# stm32f103_pin1.net
KiCad netlist of a schematic drawn in EAGLE
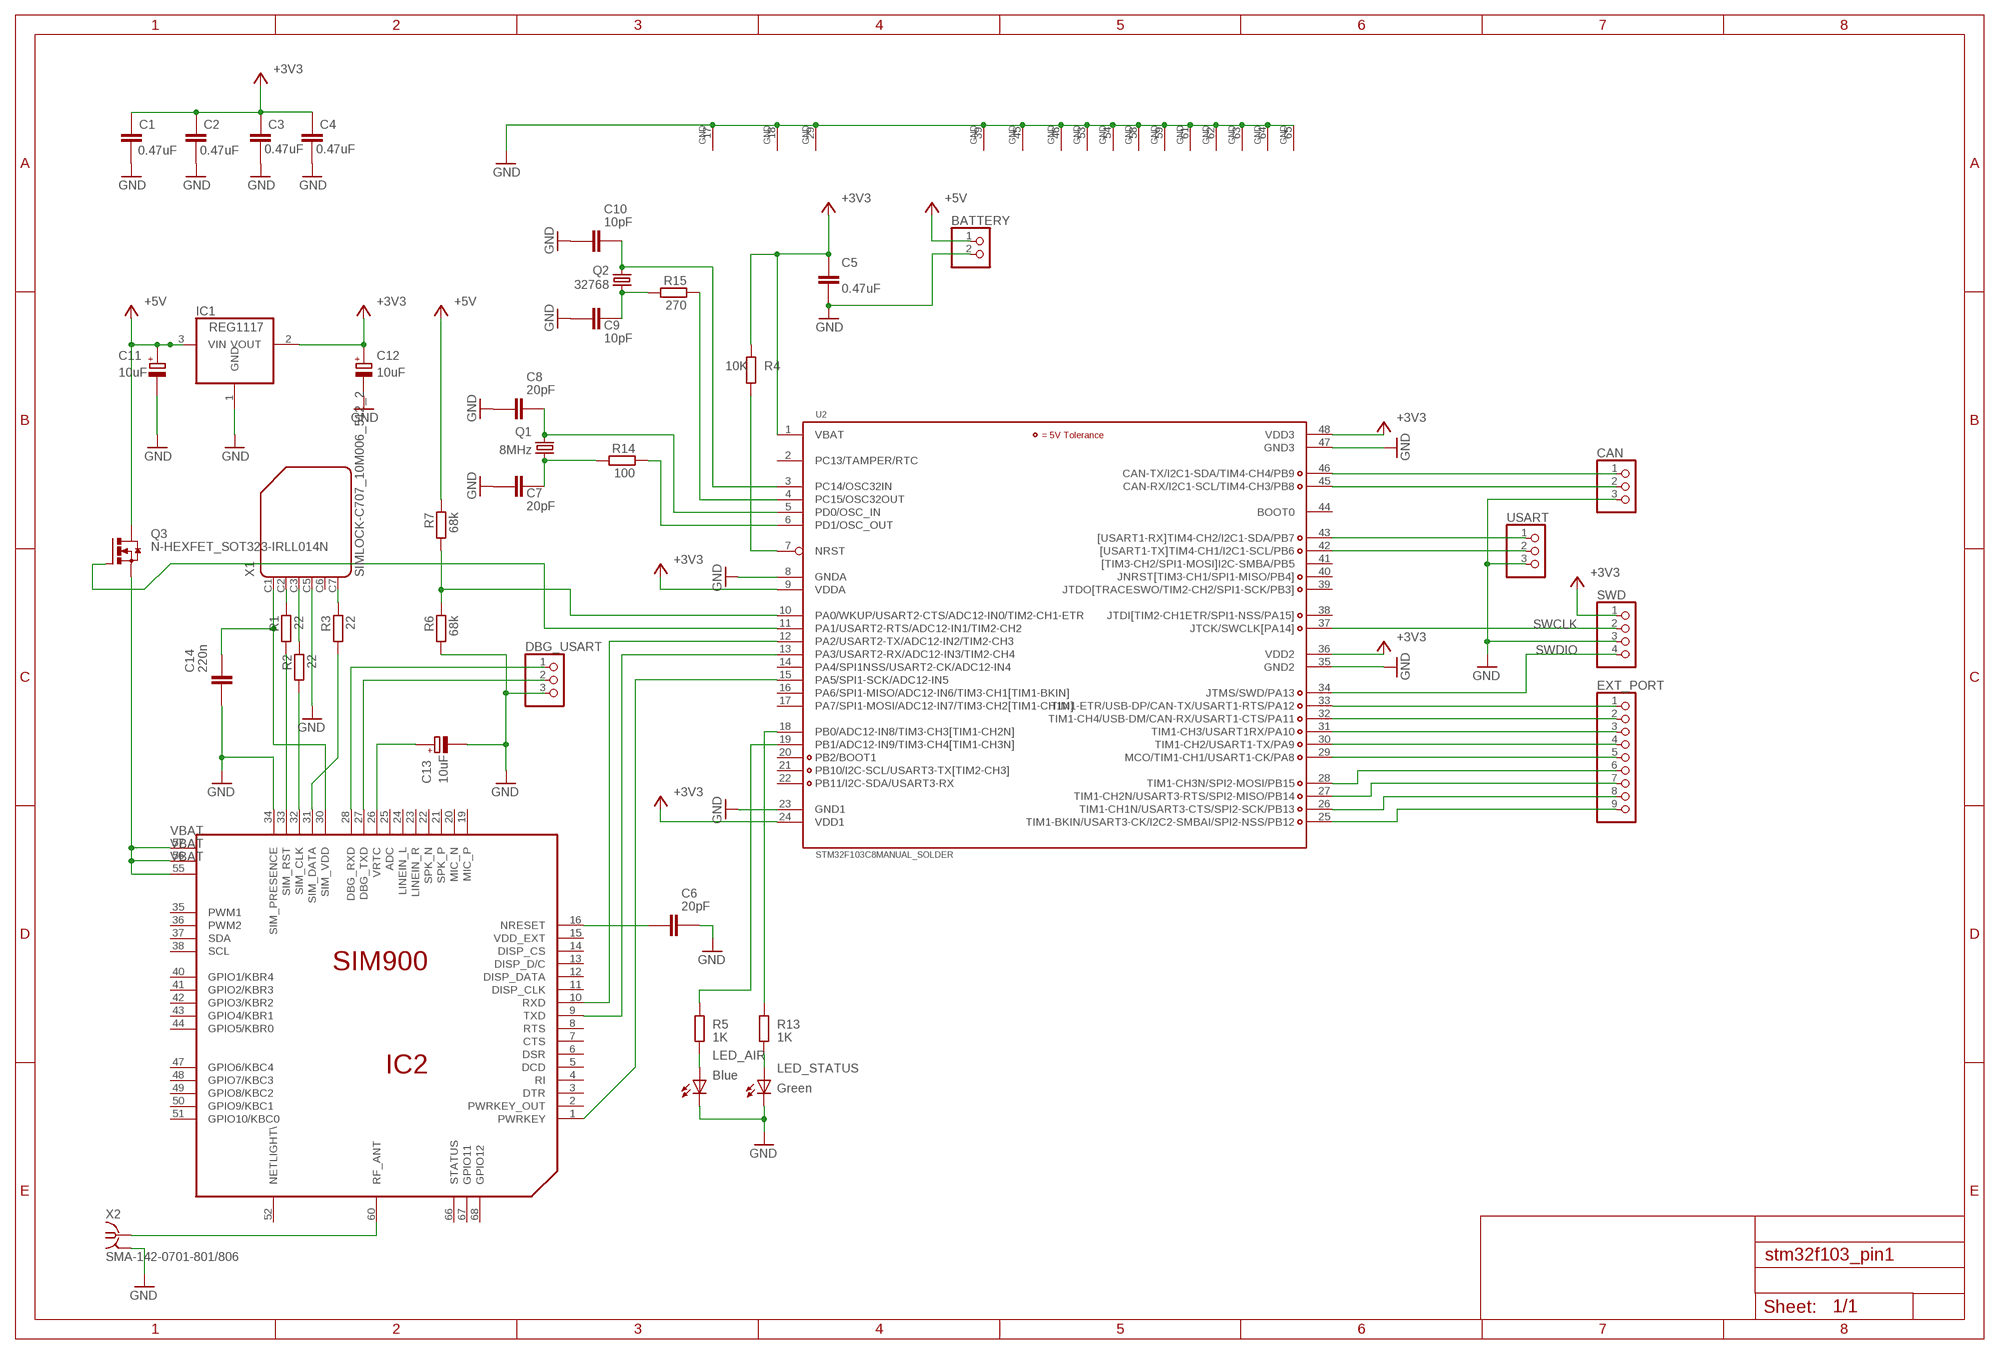
[diagram p0: schematic, sheet 1]

(export (version "E")
  (design (tool "Eeschema 10.0.6"))
  (components
    (comp (ref "BATTERY")
      (value "PINHD-1X2")
      (footprint "eagle-import:1X02")
      (libsource (lib "eagle-import") (part "PINHD-1X2"))
    )
    (comp (ref "C1")
      (value "0.47uF")
      (footprint "eagle-import:CAPC2012X145AN")
      (libsource (lib "eagle-import") (part "CAPACITOR_0805"))
    )
    (comp (ref "C2")
      (value "0.47uF")
      (footprint "eagle-import:CAPC2012X145AN")
      (libsource (lib "eagle-import") (part "CAPACITOR_0805"))
    )
    (comp (ref "C3")
      (value "0.47uF")
      (footprint "eagle-import:CAPC2012X145AN")
      (libsource (lib "eagle-import") (part "CAPACITOR_0805"))
    )
    (comp (ref "C4")
      (value "0.47uF")
      (footprint "eagle-import:CAPC2012X145AN")
      (libsource (lib "eagle-import") (part "CAPACITOR_0805"))
    )
    (comp (ref "C5")
      (value "0.47uF")
      (footprint "eagle-import:CAPC2012X145AN")
      (libsource (lib "eagle-import") (part "CAPACITOR_0805"))
    )
    (comp (ref "C6")
      (value "20pF")
      (footprint "eagle-import:CAPC2012X145AN")
      (libsource (lib "eagle-import") (part "CAPACITOR_0805"))
    )
    (comp (ref "C7")
      (value "20pF")
      (footprint "eagle-import:CAPC2012X145AN")
      (libsource (lib "eagle-import") (part "CAPACITOR_0805"))
    )
    (comp (ref "C8")
      (value "20pF")
      (footprint "eagle-import:CAPC2012X145AN")
      (libsource (lib "eagle-import") (part "CAPACITOR_0805"))
    )
    (comp (ref "C9")
      (value "10pF")
      (footprint "eagle-import:CAPC2012X145AN")
      (libsource (lib "eagle-import") (part "CAPACITOR_0805"))
    )
    (comp (ref "C10")
      (value "10pF")
      (footprint "eagle-import:CAPC2012X145AN")
      (libsource (lib "eagle-import") (part "CAPACITOR_0805"))
    )
    (comp (ref "C11")
      (value "10uF")
      (footprint "eagle-import:CAPMP3216X180N")
      (libsource (lib "eagle-import") (part "POLARISED_A_CASE"))
    )
    (comp (ref "C12")
      (value "10uF")
      (footprint "eagle-import:CAPMP3216X180N")
      (libsource (lib "eagle-import") (part "POLARISED_A_CASE"))
    )
    (comp (ref "C13")
      (value "10uF")
      (footprint "eagle-import:CAPMP3216X180N")
      (libsource (lib "eagle-import") (part "POLARISED_A_CASE"))
    )
    (comp (ref "C14")
      (value "220n")
      (footprint "eagle-import:CAPC2012X145AN")
      (libsource (lib "eagle-import") (part "CAPACITOR_0805"))
    )
    (comp (ref "CAN")
      (value "PINHD-1X3")
      (footprint "eagle-import:1X03")
      (libsource (lib "eagle-import") (part "PINHD-1X3"))
    )
    (comp (ref "DBG_USART")
      (value "PINHD-1X3")
      (footprint "eagle-import:1X03")
      (libsource (lib "eagle-import") (part "PINHD-1X3"))
    )
    (comp (ref "EXT_PORT")
      (value "PINHD-1X9")
      (footprint "eagle-import:1X09")
      (libsource (lib "eagle-import") (part "PINHD-1X9"))
    )
    (comp (ref "IC1")
      (value "REG1117")
      (footprint "eagle-import:SOT223")
      (libsource (lib "eagle-import") (part "REG1117"))
    )
    (comp (ref "IC2")
      (value "SIM900")
      (footprint "eagle-import:SIM900")
      (libsource (lib "eagle-import") (part "SIM900"))
    )
    (comp (ref "LED_AIR")
      (value "Blue")
      (footprint "eagle-import:CHIP-LED0805")
      (libsource (lib "eagle-import") (part "LEDCHIP-LED0805"))
    )
    (comp (ref "LED_STATUS")
      (value "Green")
      (footprint "eagle-import:CHIP-LED0805")
      (libsource (lib "eagle-import") (part "LEDCHIP-LED0805"))
    )
    (comp (ref "Q1")
      (value "8MHz")
      (footprint "eagle-import:HC49_S")
      (libsource (lib "eagle-import") (part "CRYSTALHC49S"))
    )
    (comp (ref "Q2")
      (value "32768")
      (footprint "eagle-import:TC38H")
      (libsource (lib "eagle-import") (part "CRYSTALTC38H"))
    )
    (comp (ref "Q3")
      (value "N-HEXFET_SOT323-IRLL014N")
      (footprint "eagle-import:SOT223")
      (libsource (lib "eagle-import") (part "N-HEXFET_?-SOT323IRLL014N"))
    )
    (comp (ref "R1")
      (value "22")
      (footprint "eagle-import:RESC2012X70N")
      (libsource (lib "eagle-import") (part "RESISTOR_0805"))
    )
    (comp (ref "R2")
      (value "22")
      (footprint "eagle-import:RESC2012X70N")
      (libsource (lib "eagle-import") (part "RESISTOR_0805"))
    )
    (comp (ref "R3")
      (value "22")
      (footprint "eagle-import:RESC2012X70N")
      (libsource (lib "eagle-import") (part "RESISTOR_0805"))
    )
    (comp (ref "R4")
      (value "10K")
      (footprint "eagle-import:RESC2012X70N")
      (libsource (lib "eagle-import") (part "RESISTOR_0805"))
    )
    (comp (ref "R5")
      (value "1K")
      (footprint "eagle-import:RESC2012X70N")
      (libsource (lib "eagle-import") (part "RESISTOR_0805"))
    )
    (comp (ref "R6")
      (value "68k")
      (footprint "eagle-import:RESC2012X70N")
      (libsource (lib "eagle-import") (part "RESISTOR_0805"))
    )
    (comp (ref "R7")
      (value "68k")
      (footprint "eagle-import:RESC2012X70N")
      (libsource (lib "eagle-import") (part "RESISTOR_0805"))
    )
    (comp (ref "R13")
      (value "1K")
      (footprint "eagle-import:RESC2012X70N")
      (libsource (lib "eagle-import") (part "RESISTOR_0805"))
    )
    (comp (ref "R14")
      (value "100")
      (footprint "eagle-import:RESC2012X70N")
      (libsource (lib "eagle-import") (part "RESISTOR_0805"))
    )
    (comp (ref "R15")
      (value "270")
      (footprint "eagle-import:RESC2012X70N")
      (libsource (lib "eagle-import") (part "RESISTOR_0805"))
    )
    (comp (ref "SWD")
      (value "PINHD-1X4")
      (footprint "eagle-import:1X04")
      (libsource (lib "eagle-import") (part "PINHD-1X4"))
    )
    (comp (ref "U2")
      (value "STM32F103C8MANUAL_SOLDER")
      (footprint "eagle-import:LQFP48_IGORL")
      (libsource (lib "eagle-import") (part "STM32F103C8MANUAL_SOLDER"))
    )
    (comp (ref "USART")
      (value "PINHD-1X3")
      (footprint "eagle-import:1X03")
      (libsource (lib "eagle-import") (part "PINHD-1X3"))
    )
    (comp (ref "X1")
      (value "SIMLOCK-C707_10M006_512_2")
      (footprint "eagle-import:C707_10M006_512_2")
      (libsource (lib "eagle-import") (part "SIMLOCK-C707_10M006_512_2"))
    )
    (comp (ref "X2")
      (value "SMA-142-0701-801/806")
      (footprint "eagle-import:J502-ND-142-0701-801_806")
      (fields (field (name "MF") "JOHNSON COMPONENTS") (field (name "MPN") "142-0701-801"))
      (libsource (lib "eagle-import") (part "SMA-142-0701-801/806"))
    )
  )
  (nets
    (net (code "1") (name "+3V3") (class "Default")
      (node (ref "C1") (pin "1") (pinfunction "1_1") (pintype "passive"))
      (node (ref "C12") (pin "+") (pinfunction "+_+") (pintype "passive"))
      (node (ref "C2") (pin "1") (pinfunction "1_1") (pintype "passive"))
      (node (ref "C3") (pin "1") (pinfunction "1_1") (pintype "passive"))
      (node (ref "C4") (pin "1") (pinfunction "1_1") (pintype "passive"))
      (node (ref "C5") (pin "1") (pinfunction "1_1") (pintype "passive"))
      (node (ref "IC1") (pin "2") (pinfunction "VOUT_2") (pintype "output"))
      (node (ref "R4") (pin "2") (pinfunction "2_2") (pintype "passive"))
      (node (ref "SWD") (pin "1") (pinfunction "1_1") (pintype "passive"))
      (node (ref "U2") (pin "1") (pinfunction "VBAT_1") (pintype "power_in"))
      (node (ref "U2") (pin "24") (pinfunction "VDD1_24") (pintype "power_in"))
      (node (ref "U2") (pin "36") (pinfunction "VDD2_36") (pintype "power_in"))
      (node (ref "U2") (pin "48") (pinfunction "VDD3_48") (pintype "power_in"))
      (node (ref "U2") (pin "9") (pinfunction "VDDA_9") (pintype "power_in"))
    )
    (net (code "2") (name "+5V") (class "Default")
      (node (ref "BATTERY") (pin "1") (pinfunction "1_1") (pintype "passive"))
      (node (ref "C11") (pin "+") (pinfunction "+_+") (pintype "passive"))
      (node (ref "IC1") (pin "3") (pinfunction "VIN_3") (pintype "input"))
      (node (ref "Q3") (pin "4") (pinfunction "D_4") (pintype "passive"))
      (node (ref "R7") (pin "1") (pinfunction "1_1") (pintype "passive"))
    )
    (net (code "3") (name "GND") (class "Default")
      (node (ref "BATTERY") (pin "2") (pinfunction "2_2") (pintype "passive"))
      (node (ref "C1") (pin "2") (pinfunction "2_2") (pintype "passive"))
      (node (ref "C10") (pin "2") (pinfunction "2_2") (pintype "passive"))
      (node (ref "C11") (pin "-") (pinfunction "-_-") (pintype "passive"))
      (node (ref "C12") (pin "-") (pinfunction "-_-") (pintype "passive"))
      (node (ref "C13") (pin "-") (pinfunction "-_-") (pintype "passive"))
      (node (ref "C14") (pin "2") (pinfunction "2_2") (pintype "passive"))
      (node (ref "C2") (pin "2") (pinfunction "2_2") (pintype "passive"))
      (node (ref "C3") (pin "2") (pinfunction "2_2") (pintype "passive"))
      (node (ref "C4") (pin "2") (pinfunction "2_2") (pintype "passive"))
      (node (ref "C5") (pin "2") (pinfunction "2_2") (pintype "passive"))
      (node (ref "C6") (pin "1") (pinfunction "1_1") (pintype "passive"))
      (node (ref "C7") (pin "2") (pinfunction "2_2") (pintype "passive"))
      (node (ref "C8") (pin "2") (pinfunction "2_2") (pintype "passive"))
      (node (ref "C9") (pin "2") (pinfunction "2_2") (pintype "passive"))
      (node (ref "CAN") (pin "3") (pinfunction "3_3") (pintype "passive"))
      (node (ref "DBG_USART") (pin "3") (pinfunction "3_3") (pintype "passive"))
      (node (ref "IC1") (pin "1") (pinfunction "GND_1") (pintype "power_in"))
      (node (ref "IC2") (pin "17") (pinfunction "GND_17") (pintype "power_in"))
      (node (ref "IC2") (pin "18") (pinfunction "GND_18") (pintype "power_in"))
      (node (ref "IC2") (pin "29") (pinfunction "GND_29") (pintype "power_in"))
      (node (ref "IC2") (pin "34") (pinfunction "SIM_PRESENCE_34") (pintype "bidirectional"))
      (node (ref "IC2") (pin "39") (pinfunction "GND_39") (pintype "power_in"))
      (node (ref "IC2") (pin "45") (pinfunction "GND_45") (pintype "power_in"))
      (node (ref "IC2") (pin "46") (pinfunction "GND_46") (pintype "power_in"))
      (node (ref "IC2") (pin "53") (pinfunction "GND_53") (pintype "power_in"))
      (node (ref "IC2") (pin "54") (pinfunction "GND_54") (pintype "power_in"))
      (node (ref "IC2") (pin "58") (pinfunction "GND_58") (pintype "power_in"))
      (node (ref "IC2") (pin "59") (pinfunction "GND_59") (pintype "power_in"))
      (node (ref "IC2") (pin "61") (pinfunction "GND_61") (pintype "power_in"))
      (node (ref "IC2") (pin "62") (pinfunction "GND_62") (pintype "power_in"))
      (node (ref "IC2") (pin "63") (pinfunction "GND_63") (pintype "power_in"))
      (node (ref "IC2") (pin "64") (pinfunction "GND_64") (pintype "power_in"))
      (node (ref "IC2") (pin "65") (pinfunction "GND_65") (pintype "power_in"))
      (node (ref "LED_AIR") (pin "C") (pinfunction "C_C") (pintype "passive"))
      (node (ref "LED_STATUS") (pin "C") (pinfunction "C_C") (pintype "passive"))
      (node (ref "R6") (pin "2") (pinfunction "2_2") (pintype "passive"))
      (node (ref "SWD") (pin "3") (pinfunction "3_3") (pintype "passive"))
      (node (ref "U2") (pin "23") (pinfunction "GND1_23") (pintype "power_in"))
      (node (ref "U2") (pin "35") (pinfunction "GND2_35") (pintype "power_in"))
      (node (ref "U2") (pin "47") (pinfunction "GND3_47") (pintype "power_in"))
      (node (ref "U2") (pin "8") (pinfunction "GNDA_8") (pintype "power_in"))
      (node (ref "USART") (pin "3") (pinfunction "3_3") (pintype "passive"))
      (node (ref "X1") (pin "C5") (pinfunction "4_C5") (pintype "passive"))
      (node (ref "X2") (pin "G@1") (pinfunction "GND_G@1") (pintype "power_in"))
    )
    (net (code "4") (name "Net-(C7-Pad1)") (class "Default")
      (node (ref "C7") (pin "1") (pinfunction "1_1") (pintype "passive"))
      (node (ref "Q1") (pin "1") (pinfunction "1_1") (pintype "passive"))
      (node (ref "R14") (pin "2") (pinfunction "2_2") (pintype "passive"))
    )
    (net (code "5") (name "Net-(C9-Pad1)") (class "Default")
      (node (ref "C9") (pin "1") (pinfunction "1_1") (pintype "passive"))
      (node (ref "Q2") (pin "1") (pinfunction "1_1") (pintype "passive"))
      (node (ref "R15") (pin "2") (pinfunction "2_2") (pintype "passive"))
    )
    (net (code "6") (name "Net-(IC2A-DBG_RXD)") (class "Default")
      (node (ref "DBG_USART") (pin "1") (pinfunction "1_1") (pintype "passive"))
      (node (ref "IC2") (pin "28") (pinfunction "DBG_RXD_28") (pintype "bidirectional"))
    )
    (net (code "7") (name "Net-(IC2A-DBG_TXD)") (class "Default")
      (node (ref "DBG_USART") (pin "2") (pinfunction "2_2") (pintype "passive"))
      (node (ref "IC2") (pin "27") (pinfunction "DBG_TXD_27") (pintype "bidirectional"))
    )
    (net (code "8") (name "Net-(IC2A-NRESET)") (class "Default")
      (node (ref "C6") (pin "2") (pinfunction "2_2") (pintype "passive"))
      (node (ref "IC2") (pin "16") (pinfunction "NRESET_16") (pintype "bidirectional"))
    )
    (net (code "9") (name "Net-(IC2A-PWRKEY)") (class "Default")
      (node (ref "IC2") (pin "1") (pinfunction "PWRKEY_1") (pintype "bidirectional"))
      (node (ref "U2") (pin "15") (pinfunction "PA5/SPI1-SCK/ADC12-IN5_15") (pintype "bidirectional"))
    )
    (net (code "10") (name "Net-(IC2A-RF_ANT)") (class "Default")
      (node (ref "IC2") (pin "60") (pinfunction "RF_ANT_60") (pintype "bidirectional"))
      (node (ref "X2") (pin "1") (pinfunction "1_1") (pintype "passive"))
    )
    (net (code "11") (name "Net-(IC2A-RXD)") (class "Default")
      (node (ref "IC2") (pin "10") (pinfunction "RXD_10") (pintype "bidirectional"))
      (node (ref "U2") (pin "12") (pinfunction "PA2/USART2-TX/ADC12-IN2/TIM2-CH3_12") (pintype "bidirectional"))
    )
    (net (code "12") (name "Net-(IC2A-SIM_CLK)") (class "Default")
      (node (ref "IC2") (pin "32") (pinfunction "SIM_CLK_32") (pintype "bidirectional"))
      (node (ref "R2") (pin "2") (pinfunction "2_2") (pintype "passive"))
    )
    (net (code "13") (name "Net-(IC2A-SIM_DATA)") (class "Default")
      (node (ref "IC2") (pin "31") (pinfunction "SIM_DATA_31") (pintype "bidirectional"))
      (node (ref "R3") (pin "2") (pinfunction "2_2") (pintype "passive"))
    )
    (net (code "14") (name "Net-(IC2A-SIM_RST)") (class "Default")
      (node (ref "IC2") (pin "33") (pinfunction "SIM_RST_33") (pintype "bidirectional"))
      (node (ref "R1") (pin "2") (pinfunction "2_2") (pintype "passive"))
    )
    (net (code "15") (name "Net-(IC2A-SIM_VDD)") (class "Default")
      (node (ref "C14") (pin "1") (pinfunction "1_1") (pintype "passive"))
      (node (ref "IC2") (pin "30") (pinfunction "SIM_VDD_30") (pintype "bidirectional"))
      (node (ref "X1") (pin "C1") (pinfunction "1_C1") (pintype "passive"))
    )
    (net (code "16") (name "Net-(IC2A-TXD)") (class "Default")
      (node (ref "IC2") (pin "9") (pinfunction "TXD_9") (pintype "bidirectional"))
      (node (ref "U2") (pin "13") (pinfunction "PA3/USART2-RX/ADC12-IN3/TIM2-CH4_13") (pintype "bidirectional"))
    )
    (net (code "17") (name "Net-(IC2A-VRTC)") (class "Default")
      (node (ref "C13") (pin "+") (pinfunction "+_+") (pintype "passive"))
      (node (ref "IC2") (pin "26") (pinfunction "VRTC_26") (pintype "bidirectional"))
    )
    (net (code "18") (name "Net-(IC2Q-VBAT)") (class "Default")
      (node (ref "IC2") (pin "55") (pinfunction "VBAT_55") (pintype "power_in"))
      (node (ref "IC2") (pin "56") (pinfunction "VBAT_56") (pintype "power_in"))
      (node (ref "IC2") (pin "57") (pinfunction "VBAT_57") (pintype "power_in"))
      (node (ref "Q3") (pin "3") (pinfunction "S_3") (pintype "passive"))
    )
    (net (code "19") (name "Net-(LED_AIR-PadA)") (class "Default")
      (node (ref "LED_AIR") (pin "A") (pinfunction "A_A") (pintype "passive"))
      (node (ref "R5") (pin "1") (pinfunction "1_1") (pintype "passive"))
    )
    (net (code "20") (name "Net-(LED_STATUS-PadA)") (class "Default")
      (node (ref "LED_STATUS") (pin "A") (pinfunction "A_A") (pintype "passive"))
      (node (ref "R13") (pin "1") (pinfunction "1_1") (pintype "passive"))
    )
    (net (code "21") (name "Net-(Q3-G)") (class "Default")
      (node (ref "Q3") (pin "1") (pinfunction "G_1") (pintype "passive"))
      (node (ref "U2") (pin "11") (pinfunction "PA1/USART2-RTS/ADC12-IN1/TIM2-CH2_11") (pintype "bidirectional"))
    )
    (net (code "22") (name "Net-(U2-CAN-RX{slash}I2C1-SCL{slash}TIM4-CH3{slash}PB8)") (class "Default")
      (node (ref "CAN") (pin "2") (pinfunction "2_2") (pintype "passive"))
      (node (ref "U2") (pin "45") (pinfunction "CAN-RX/I2C1-SCL/TIM4-CH3/PB8_45") (pintype "bidirectional"))
    )
    (net (code "23") (name "Net-(U2-CAN-TX{slash}I2C1-SDA{slash}TIM4-CH4{slash}PB9)") (class "Default")
      (node (ref "CAN") (pin "1") (pinfunction "1_1") (pintype "passive"))
      (node (ref "U2") (pin "46") (pinfunction "CAN-TX/I2C1-SDA/TIM4-CH4/PB9_46") (pintype "bidirectional"))
    )
    (net (code "24") (name "Net-(U2-JTCK{slash}SWCLK[PA14])") (class "Default")
      (node (ref "SWD") (pin "2") (pinfunction "2_2") (pintype "passive"))
      (node (ref "U2") (pin "37") (pinfunction "JTCK/SWCLK[PA14]_37") (pintype "bidirectional"))
    )
    (net (code "25") (name "Net-(U2-JTMS{slash}SWD{slash}PA13)") (class "Default")
      (node (ref "SWD") (pin "4") (pinfunction "4_4") (pintype "passive"))
      (node (ref "U2") (pin "34") (pinfunction "JTMS/SWD/PA13_34") (pintype "bidirectional"))
    )
    (net (code "26") (name "Net-(U2-MCO{slash}TIM1-CH1{slash}USART1-CK{slash}PA8)") (class "Default")
      (node (ref "EXT_PORT") (pin "5") (pinfunction "5_5") (pintype "passive"))
      (node (ref "U2") (pin "29") (pinfunction "MCO/TIM1-CH1/USART1-CK/PA8_29") (pintype "bidirectional"))
    )
    (net (code "27") (name "Net-(U2-NRST)") (class "Default")
      (node (ref "R4") (pin "1") (pinfunction "1_1") (pintype "passive"))
      (node (ref "U2") (pin "7") (pinfunction "NRST_7") (pintype "bidirectional"))
    )
    (net (code "28") (name "Net-(U2-PA0{slash}WKUP{slash}USART2-CTS{slash}ADC12-IN0{slash}TIM2-CH1-ETR)") (class "Default")
      (node (ref "R6") (pin "1") (pinfunction "1_1") (pintype "passive"))
      (node (ref "R7") (pin "2") (pinfunction "2_2") (pintype "passive"))
      (node (ref "U2") (pin "10") (pinfunction "PA0/WKUP/USART2-CTS/ADC12-IN0/TIM2-CH1-ETR_10") (pintype "bidirectional"))
    )
    (net (code "29") (name "Net-(U2-PB0{slash}ADC12-IN8{slash}TIM3-CH3[TIM1-CH2N])") (class "Default")
      (node (ref "R13") (pin "2") (pinfunction "2_2") (pintype "passive"))
      (node (ref "U2") (pin "18") (pinfunction "PB0/ADC12-IN8/TIM3-CH3[TIM1-CH2N]_18") (pintype "bidirectional"))
    )
    (net (code "30") (name "Net-(U2-PB1{slash}ADC12-IN9{slash}TIM3-CH4[TIM1-CH3N])") (class "Default")
      (node (ref "R5") (pin "2") (pinfunction "2_2") (pintype "passive"))
      (node (ref "U2") (pin "19") (pinfunction "PB1/ADC12-IN9/TIM3-CH4[TIM1-CH3N]_19") (pintype "bidirectional"))
    )
    (net (code "31") (name "Net-(U2-PC14{slash}OSC32IN)") (class "Default")
      (node (ref "C10") (pin "1") (pinfunction "1_1") (pintype "passive"))
      (node (ref "Q2") (pin "2") (pinfunction "2_2") (pintype "passive"))
      (node (ref "U2") (pin "3") (pinfunction "PC14/OSC32IN_3") (pintype "bidirectional"))
    )
    (net (code "32") (name "Net-(U2-PC15{slash}OSC32OUT)") (class "Default")
      (node (ref "R15") (pin "1") (pinfunction "1_1") (pintype "passive"))
      (node (ref "U2") (pin "4") (pinfunction "PC15/OSC32OUT_4") (pintype "bidirectional"))
    )
    (net (code "33") (name "Net-(U2-PD0{slash}OSC_IN)") (class "Default")
      (node (ref "C8") (pin "1") (pinfunction "1_1") (pintype "passive"))
      (node (ref "Q1") (pin "2") (pinfunction "2_2") (pintype "passive"))
      (node (ref "U2") (pin "5") (pinfunction "PD0/OSC_IN_5") (pintype "bidirectional"))
    )
    (net (code "34") (name "Net-(U2-PD1{slash}OSC_OUT)") (class "Default")
      (node (ref "R14") (pin "1") (pinfunction "1_1") (pintype "passive"))
      (node (ref "U2") (pin "6") (pinfunction "PD1/OSC_OUT_6") (pintype "bidirectional"))
    )
    (net (code "35") (name "Net-(U2-TIM1-BKIN{slash}USART3-CK{slash}I2C2-SMBAI{slash}SPI2-NSS{slash}PB12)") (class "Default")
      (node (ref "EXT_PORT") (pin "9") (pinfunction "9_9") (pintype "passive"))
      (node (ref "U2") (pin "25") (pinfunction "TIM1-BKIN/USART3-CK/I2C2-SMBAI/SPI2-NSS/PB12_25") (pintype "bidirectional"))
    )
    (net (code "36") (name "Net-(U2-TIM1-CH1N{slash}USART3-CTS{slash}SPI2-SCK{slash}PB13)") (class "Default")
      (node (ref "EXT_PORT") (pin "8") (pinfunction "8_8") (pintype "passive"))
      (node (ref "U2") (pin "26") (pinfunction "TIM1-CH1N/USART3-CTS/SPI2-SCK/PB13_26") (pintype "bidirectional"))
    )
    (net (code "37") (name "Net-(U2-TIM1-CH2N{slash}USART3-RTS{slash}SPI2-MISO{slash}PB14)") (class "Default")
      (node (ref "EXT_PORT") (pin "7") (pinfunction "7_7") (pintype "passive"))
      (node (ref "U2") (pin "27") (pinfunction "TIM1-CH2N/USART3-RTS/SPI2-MISO/PB14_27") (pintype "bidirectional"))
    )
    (net (code "38") (name "Net-(U2-TIM1-CH2{slash}USART1-TX{slash}PA9)") (class "Default")
      (node (ref "EXT_PORT") (pin "4") (pinfunction "4_4") (pintype "passive"))
      (node (ref "U2") (pin "30") (pinfunction "TIM1-CH2/USART1-TX/PA9_30") (pintype "bidirectional"))
    )
    (net (code "39") (name "Net-(U2-TIM1-CH3N{slash}SPI2-MOSI{slash}PB15)") (class "Default")
      (node (ref "EXT_PORT") (pin "6") (pinfunction "6_6") (pintype "passive"))
      (node (ref "U2") (pin "28") (pinfunction "TIM1-CH3N/SPI2-MOSI/PB15_28") (pintype "bidirectional"))
    )
    (net (code "40") (name "Net-(U2-TIM1-CH3{slash}USART1RX{slash}PA10)") (class "Default")
      (node (ref "EXT_PORT") (pin "3") (pinfunction "3_3") (pintype "passive"))
      (node (ref "U2") (pin "31") (pinfunction "TIM1-CH3/USART1RX/PA10_31") (pintype "bidirectional"))
    )
    (net (code "41") (name "Net-(U2-TIM1-CH4{slash}USB-DM{slash}CAN-RX{slash}USART1-CTS{slash}PA11)") (class "Default")
      (node (ref "EXT_PORT") (pin "2") (pinfunction "2_2") (pintype "passive"))
      (node (ref "U2") (pin "32") (pinfunction "TIM1-CH4/USB-DM/CAN-RX/USART1-CTS/PA11_32") (pintype "bidirectional"))
    )
    (net (code "42") (name "Net-(U2-TIM1-ETR{slash}USB-DP{slash}CAN-TX{slash}USART1-RTS{slash}PA12)") (class "Default")
      (node (ref "EXT_PORT") (pin "1") (pinfunction "1_1") (pintype "passive"))
      (node (ref "U2") (pin "33") (pinfunction "TIM1-ETR/USB-DP/CAN-TX/USART1-RTS/PA12_33") (pintype "bidirectional"))
    )
    (net (code "43") (name "Net-(U2-[USART1-RX]TIM4-CH2{slash}I2C1-SDA{slash}PB7)") (class "Default")
      (node (ref "U2") (pin "43") (pinfunction "[USART1-RX]TIM4-CH2/I2C1-SDA/PB7_43") (pintype "bidirectional"))
      (node (ref "USART") (pin "1") (pinfunction "1_1") (pintype "passive"))
    )
    (net (code "44") (name "Net-(U2-[USART1-TX]TIM4-CH1{slash}I2C1-SCL{slash}PB6)") (class "Default")
      (node (ref "U2") (pin "42") (pinfunction "[USART1-TX]TIM4-CH1/I2C1-SCL/PB6_42") (pintype "bidirectional"))
      (node (ref "USART") (pin "2") (pinfunction "2_2") (pintype "passive"))
    )
    (net (code "45") (name "Net-(X1-2)") (class "Default")
      (node (ref "R1") (pin "1") (pinfunction "1_1") (pintype "passive"))
      (node (ref "X1") (pin "C2") (pinfunction "2_C2") (pintype "passive"))
    )
    (net (code "46") (name "Net-(X1-3)") (class "Default")
      (node (ref "R2") (pin "1") (pinfunction "1_1") (pintype "passive"))
      (node (ref "X1") (pin "C3") (pinfunction "3_C3") (pintype "passive"))
    )
    (net (code "47") (name "Net-(X1-6)") (class "Default")
      (node (ref "R3") (pin "1") (pinfunction "1_1") (pintype "passive"))
      (node (ref "X1") (pin "C7") (pinfunction "6_C7") (pintype "passive"))
    )
    (net (code "48") (name "unconnected-(IC2A-ADC-Pad25)") (class "Default")
      (node (ref "IC2") (pin "25") (pinfunction "ADC_25") (pintype "bidirectional"))
    )
    (net (code "49") (name "unconnected-(IC2A-CTS-Pad7)") (class "Default")
      (node (ref "IC2") (pin "7") (pinfunction "CTS_7") (pintype "bidirectional"))
    )
    (net (code "50") (name "unconnected-(IC2A-DCD-Pad5)") (class "Default")
      (node (ref "IC2") (pin "5") (pinfunction "DCD_5") (pintype "bidirectional"))
    )
    (net (code "51") (name "unconnected-(IC2A-DISP_CLK-Pad11)") (class "Default")
      (node (ref "IC2") (pin "11") (pinfunction "DISP_CLK_11") (pintype "bidirectional"))
    )
    (net (code "52") (name "unconnected-(IC2A-DISP_CS-Pad14)") (class "Default")
      (node (ref "IC2") (pin "14") (pinfunction "DISP_CS_14") (pintype "bidirectional"))
    )
    (net (code "53") (name "unconnected-(IC2A-DISP_DATA-Pad12)") (class "Default")
      (node (ref "IC2") (pin "12") (pinfunction "DISP_DATA_12") (pintype "bidirectional"))
    )
    (net (code "54") (name "unconnected-(IC2A-DISP_D{slash}C-Pad13)") (class "Default")
      (node (ref "IC2") (pin "13") (pinfunction "DISP_D/C_13") (pintype "bidirectional"))
    )
    (net (code "55") (name "unconnected-(IC2A-DSR-Pad6)") (class "Default")
      (node (ref "IC2") (pin "6") (pinfunction "DSR_6") (pintype "bidirectional"))
    )
    (net (code "56") (name "unconnected-(IC2A-DTR-Pad3)") (class "Default")
      (node (ref "IC2") (pin "3") (pinfunction "DTR_3") (pintype "bidirectional"))
    )
    (net (code "57") (name "unconnected-(IC2A-GPIO1{slash}KBR4-Pad40)") (class "Default")
      (node (ref "IC2") (pin "40") (pinfunction "GPIO1/KBR4_40") (pintype "bidirectional"))
    )
    (net (code "58") (name "unconnected-(IC2A-GPIO2{slash}KBR3-Pad41)") (class "Default")
      (node (ref "IC2") (pin "41") (pinfunction "GPIO2/KBR3_41") (pintype "bidirectional"))
    )
    (net (code "59") (name "unconnected-(IC2A-GPIO3{slash}KBR2-Pad42)") (class "Default")
      (node (ref "IC2") (pin "42") (pinfunction "GPIO3/KBR2_42") (pintype "bidirectional"))
    )
    (net (code "60") (name "unconnected-(IC2A-GPIO4{slash}KBR1-Pad43)") (class "Default")
      (node (ref "IC2") (pin "43") (pinfunction "GPIO4/KBR1_43") (pintype "bidirectional"))
    )
    (net (code "61") (name "unconnected-(IC2A-GPIO5{slash}KBR0-Pad44)") (class "Default")
      (node (ref "IC2") (pin "44") (pinfunction "GPIO5/KBR0_44") (pintype "bidirectional"))
    )
    (net (code "62") (name "unconnected-(IC2A-GPIO6{slash}KBC4-Pad47)") (class "Default")
      (node (ref "IC2") (pin "47") (pinfunction "GPIO6/KBC4_47") (pintype "bidirectional"))
    )
    (net (code "63") (name "unconnected-(IC2A-GPIO7{slash}KBC3-Pad48)") (class "Default")
      (node (ref "IC2") (pin "48") (pinfunction "GPIO7/KBC3_48") (pintype "bidirectional"))
    )
    (net (code "64") (name "unconnected-(IC2A-GPIO8{slash}KBC2-Pad49)") (class "Default")
      (node (ref "IC2") (pin "49") (pinfunction "GPIO8/KBC2_49") (pintype "bidirectional"))
    )
    (net (code "65") (name "unconnected-(IC2A-GPIO9{slash}KBC1-Pad50)") (class "Default")
      (node (ref "IC2") (pin "50") (pinfunction "GPIO9/KBC1_50") (pintype "bidirectional"))
    )
    (net (code "66") (name "unconnected-(IC2A-GPIO10{slash}KBC0-Pad51)") (class "Default")
      (node (ref "IC2") (pin "51") (pinfunction "GPIO10/KBC0_51") (pintype "bidirectional"))
    )
    (net (code "67") (name "unconnected-(IC2A-GPIO11-Pad67)") (class "Default")
      (node (ref "IC2") (pin "67") (pinfunction "GPIO11_67") (pintype "bidirectional"))
    )
    (net (code "68") (name "unconnected-(IC2A-GPIO12-Pad68)") (class "Default")
      (node (ref "IC2") (pin "68") (pinfunction "GPIO12_68") (pintype "bidirectional"))
    )
    (net (code "69") (name "unconnected-(IC2A-LINEIN_L-Pad24)") (class "Default")
      (node (ref "IC2") (pin "24") (pinfunction "LINEIN_L_24") (pintype "bidirectional"))
    )
    (net (code "70") (name "unconnected-(IC2A-LINEIN_R-Pad23)") (class "Default")
      (node (ref "IC2") (pin "23") (pinfunction "LINEIN_R_23") (pintype "bidirectional"))
    )
    (net (code "71") (name "unconnected-(IC2A-MIC_N-Pad20)") (class "Default")
      (node (ref "IC2") (pin "20") (pinfunction "MIC_N_20") (pintype "bidirectional"))
    )
    (net (code "72") (name "unconnected-(IC2A-MIC_P-Pad19)") (class "Default")
      (node (ref "IC2") (pin "19") (pinfunction "MIC_P_19") (pintype "bidirectional"))
    )
    (net (code "73") (name "unconnected-(IC2A-NETLIGHT\\-Pad52)") (class "Default")
      (node (ref "IC2") (pin "52") (pinfunction "NETLIGHT\\_52") (pintype "bidirectional"))
    )
    (net (code "74") (name "unconnected-(IC2A-PWM1-Pad35)") (class "Default")
      (node (ref "IC2") (pin "35") (pinfunction "PWM1_35") (pintype "bidirectional"))
    )
    (net (code "75") (name "unconnected-(IC2A-PWM2-Pad36)") (class "Default")
      (node (ref "IC2") (pin "36") (pinfunction "PWM2_36") (pintype "bidirectional"))
    )
    (net (code "76") (name "unconnected-(IC2A-PWRKEY_OUT-Pad2)") (class "Default")
      (node (ref "IC2") (pin "2") (pinfunction "PWRKEY_OUT_2") (pintype "bidirectional"))
    )
    (net (code "77") (name "unconnected-(IC2A-RI-Pad4)") (class "Default")
      (node (ref "IC2") (pin "4") (pinfunction "RI_4") (pintype "bidirectional"))
    )
    (net (code "78") (name "unconnected-(IC2A-RTS-Pad8)") (class "Default")
      (node (ref "IC2") (pin "8") (pinfunction "RTS_8") (pintype "bidirectional"))
    )
    (net (code "79") (name "unconnected-(IC2A-SCL-Pad38)") (class "Default")
      (node (ref "IC2") (pin "38") (pinfunction "SCL_38") (pintype "bidirectional"))
    )
    (net (code "80") (name "unconnected-(IC2A-SDA-Pad37)") (class "Default")
      (node (ref "IC2") (pin "37") (pinfunction "SDA_37") (pintype "bidirectional"))
    )
    (net (code "81") (name "unconnected-(IC2A-SPK_N-Pad22)") (class "Default")
      (node (ref "IC2") (pin "22") (pinfunction "SPK_N_22") (pintype "bidirectional"))
    )
    (net (code "82") (name "unconnected-(IC2A-SPK_P-Pad21)") (class "Default")
      (node (ref "IC2") (pin "21") (pinfunction "SPK_P_21") (pintype "bidirectional"))
    )
    (net (code "83") (name "unconnected-(IC2A-STATUS-Pad66)") (class "Default")
      (node (ref "IC2") (pin "66") (pinfunction "STATUS_66") (pintype "bidirectional"))
    )
    (net (code "84") (name "unconnected-(IC2A-VDD_EXT-Pad15)") (class "Default")
      (node (ref "IC2") (pin "15") (pinfunction "VDD_EXT_15") (pintype "bidirectional"))
    )
    (net (code "85") (name "unconnected-(U2-BOOT0-Pad44)") (class "Default")
      (node (ref "U2") (pin "44") (pinfunction "BOOT0_44") (pintype "bidirectional"))
    )
    (net (code "86") (name "unconnected-(U2-JNRST[TIM3-CH1{slash}SPI1-MISO{slash}PB4]-Pad40)") (class "Default")
      (node (ref "U2") (pin "40") (pinfunction "JNRST[TIM3-CH1/SPI1-MISO/PB4]_40") (pintype "bidirectional"))
    )
    (net (code "87") (name "unconnected-(U2-JTDI[TIM2-CH1ETR{slash}SPI1-NSS{slash}PA15]-Pad38)") (class "Default")
      (node (ref "U2") (pin "38") (pinfunction "JTDI[TIM2-CH1ETR/SPI1-NSS/PA15]_38") (pintype "bidirectional"))
    )
    (net (code "88") (name "unconnected-(U2-JTDO[TRACESWO{slash}TIM2-CH2{slash}SPI1-SCK{slash}PB3]-Pad39)") (class "Default")
      (node (ref "U2") (pin "39") (pinfunction "JTDO[TRACESWO/TIM2-CH2/SPI1-SCK/PB3]_39") (pintype "bidirectional"))
    )
    (net (code "89") (name "unconnected-(U2-PA4{slash}SPI1NSS{slash}USART2-CK{slash}ADC12-IN4-Pad14)") (class "Default")
      (node (ref "U2") (pin "14") (pinfunction "PA4/SPI1NSS/USART2-CK/ADC12-IN4_14") (pintype "bidirectional"))
    )
    (net (code "90") (name "unconnected-(U2-PA6{slash}SPI1-MISO{slash}ADC12-IN6{slash}TIM3-CH1[TIM1-BKIN]-Pad16)") (class "Default")
      (node (ref "U2") (pin "16") (pinfunction "PA6/SPI1-MISO/ADC12-IN6/TIM3-CH1[TIM1-BKIN]_16") (pintype "bidirectional"))
    )
    (net (code "91") (name "unconnected-(U2-PA7{slash}SPI1-MOSI{slash}ADC12-IN7{slash}TIM3-CH2[TIM1-CH1N]-Pad17)") (class "Default")
      (node (ref "U2") (pin "17") (pinfunction "PA7/SPI1-MOSI/ADC12-IN7/TIM3-CH2[TIM1-CH1N]_17") (pintype "bidirectional"))
    )
    (net (code "92") (name "unconnected-(U2-PB2{slash}BOOT1-Pad20)") (class "Default")
      (node (ref "U2") (pin "20") (pinfunction "PB2/BOOT1_20") (pintype "bidirectional"))
    )
    (net (code "93") (name "unconnected-(U2-PB10{slash}I2C-SCL{slash}USART3-TX[TIM2-CH3]-Pad21)") (class "Default")
      (node (ref "U2") (pin "21") (pinfunction "PB10/I2C-SCL/USART3-TX[TIM2-CH3]_21") (pintype "bidirectional"))
    )
    (net (code "94") (name "unconnected-(U2-PB11{slash}I2C-SDA{slash}USART3-RX-Pad22)") (class "Default")
      (node (ref "U2") (pin "22") (pinfunction "PB11/I2C-SDA/USART3-RX_22") (pintype "bidirectional"))
    )
    (net (code "95") (name "unconnected-(U2-PC13{slash}TAMPER{slash}RTC-Pad2)") (class "Default")
      (node (ref "U2") (pin "2") (pinfunction "PC13/TAMPER/RTC_2") (pintype "bidirectional"))
    )
    (net (code "96") (name "unconnected-(U2-[TIM3-CH2{slash}SPI1-MOSI]I2C-SMBA{slash}PB5-Pad41)") (class "Default")
      (node (ref "U2") (pin "41") (pinfunction "[TIM3-CH2/SPI1-MOSI]I2C-SMBA/PB5_41") (pintype "bidirectional"))
    )
    (net (code "97") (name "unconnected-(X1-5-PadC6)") (class "Default")
      (node (ref "X1") (pin "C6") (pinfunction "5_C6") (pintype "passive"))
    )
  )
)
